# arm_mcu.net
KiCad netlist of a schematic drawn in Altium Designer
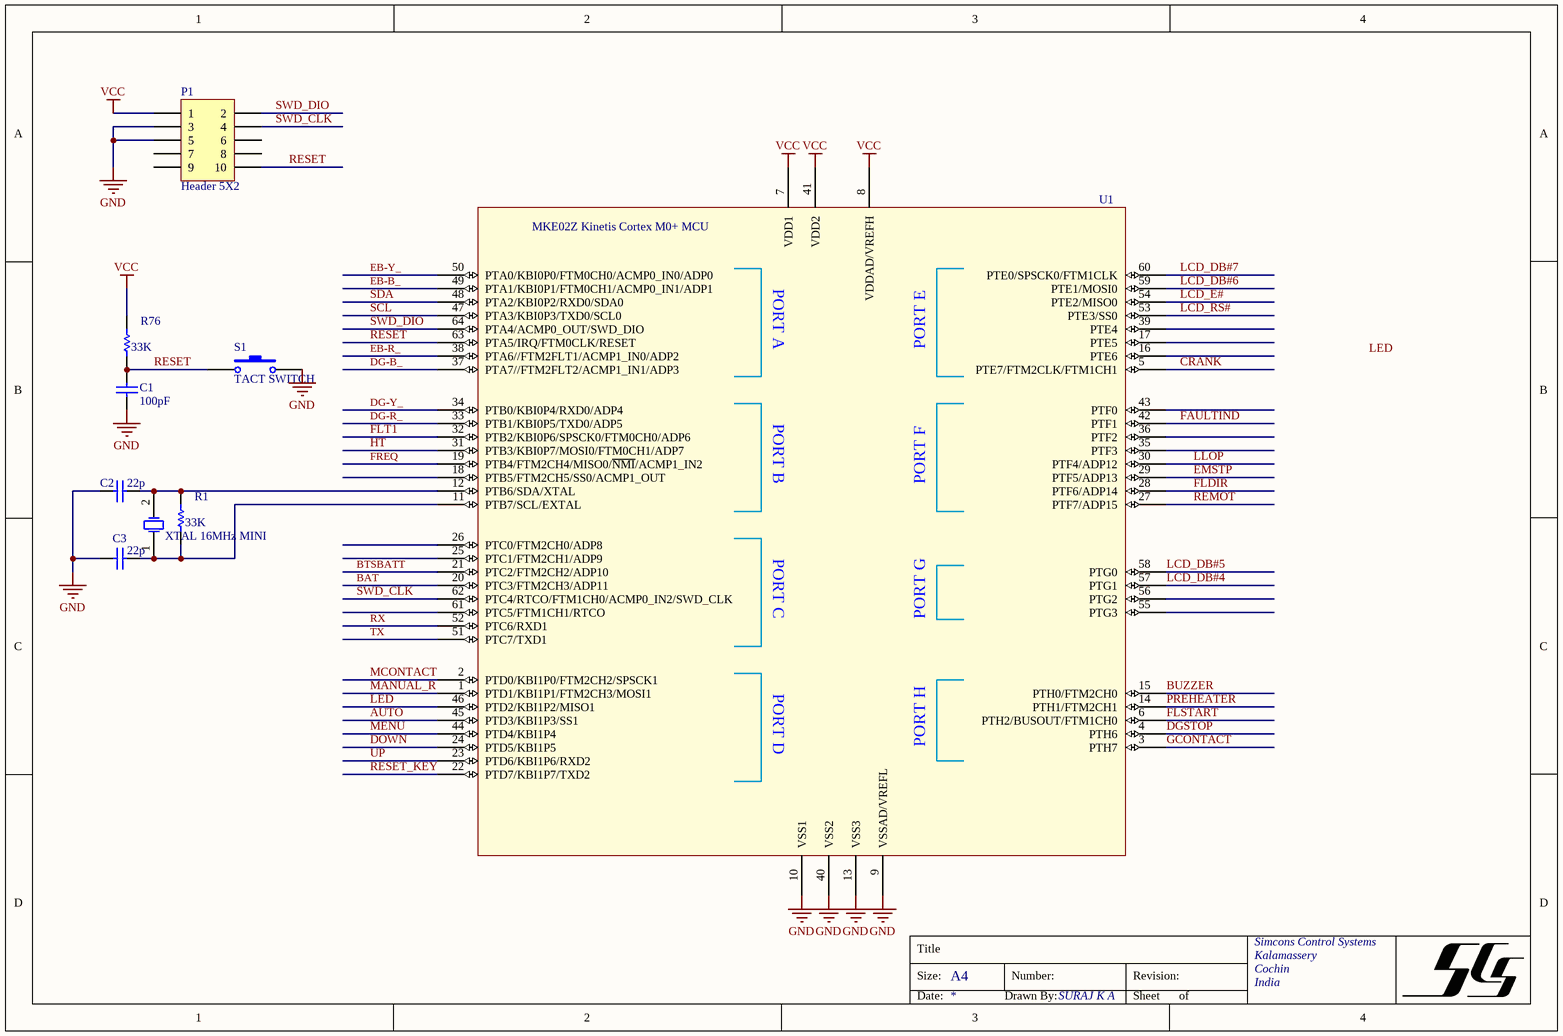
[diagram p0: arm_mcu.SchDoc]

(export (version "E")
  (design (tool "Eeschema 10.0.6"))
  (components
    (comp (ref "C1")
      (value "100pF")
      (footprint "C1206_W")
      (description "Capacitor")
      (fields (field (name "Comment") ".1uF 1206") (field (name "PUBLISHER") "Altium Limited"))
      (libsource (lib "Miscellaneous Devices") (part "Cap"))
    )
    (comp (ref "C2")
      (value "22p")
      (footprint "C1206_W")
      (description "Capacitor")
      (fields (field (name "Comment") "22pF 1206") (field (name "PUBLISHER") "Altium Limited"))
      (libsource (lib "Miscellaneous Devices") (part "Cap"))
    )
    (comp (ref "C3")
      (value "22p")
      (footprint "C1206_W")
      (description "Capacitor")
      (fields (field (name "Comment") "22pF 1206") (field (name "PUBLISHER") "Altium Limited"))
      (libsource (lib "Miscellaneous Devices") (part "Cap"))
    )
    (comp (ref "P1")
      (value "Header 5X2")
      (footprint "HDR2X5")
      (description "Header, 5-Pin, Dual row")
      (fields (field (name "PUBLISHER") "Altium Limited"))
      (libsource (lib "Miscellaneous Connectors") (part "Header 5X2"))
    )
    (comp (ref "R1")
      (value "33K")
      (footprint "R1206_W")
      (description "Resistor")
      (fields (field (name "Comment") "100K 1206") (field (name "PUBLISHER") "Altium Limited"))
      (libsource (lib "Miscellaneous Devices") (part "Res1"))
    )
    (comp (ref "R76")
      (value "33K")
      (footprint "R1206_W")
      (description "Resistor")
      (fields (field (name "Comment") "100K 1206") (field (name "PUBLISHER") "Altium Limited"))
      (libsource (lib "Miscellaneous Devices") (part "Res1"))
    )
    (comp (ref "S1")
      (value "TACT SWITCH")
      (footprint "SWSMALL")
      (description "Switch")
      (fields (field (name "PUBLISHER") "Altium Limited"))
      (libsource (lib "Miscellaneous Devices") (part "SW-PB"))
    )
    (comp (ref "U1")
      (value "MKE02Z Kinetis Cortex M0+ MCU")
      (footprint "PLQP0064GA-A_M")
      (description "32-Bit ARM Cortex M0+ RISC Core, 64KB Program Flash, 256B EEPROM, 4KB RAM, 64-Pin LQFP")
      (libsource (lib "PCB_Project1") (part "MKE02Z64"))
    )
    (comp (ref "Y1")
      (value "XTAL 16MHz MINI")
      (footprint "XTAL")
      (description "Crystal Oscillator")
      (fields (field (name "PUBLISHER") "Altium Limited"))
      (libsource (lib "Miscellaneous Devices") (part "XTAL"))
    )
  )
  (nets
    (net (code "1") (name "/AUTO") (class "Default")
      (node (ref "U1") (pin "45") (pinfunction "PTD3/KBI1P3/SS1_45") (pintype "bidirectional"))
    )
    (net (code "2") (name "/BAT") (class "Default")
      (node (ref "U1") (pin "20") (pinfunction "PTC3/FTM2CH3/ADP11_20") (pintype "bidirectional"))
    )
    (net (code "3") (name "/BTSBATT") (class "Default")
      (node (ref "U1") (pin "21") (pinfunction "PTC2/FTM2CH2/ADP10_21") (pintype "bidirectional"))
    )
    (net (code "4") (name "/BUZZER") (class "Default")
      (node (ref "U1") (pin "15") (pinfunction "PTH0/FTM2CH0_15") (pintype "bidirectional"))
    )
    (net (code "5") (name "/CRANK") (class "Default")
      (node (ref "U1") (pin "5") (pinfunction "PTE7/FTM2CLK/FTM1CH1_5") (pintype "bidirectional"))
    )
    (net (code "6") (name "/DG-B_") (class "Default")
      (node (ref "U1") (pin "37") (pinfunction "PTA7//FTM2FLT2/ACMP1_IN1/ADP3_37") (pintype "bidirectional"))
    )
    (net (code "7") (name "/DG-R_") (class "Default")
      (node (ref "U1") (pin "33") (pinfunction "PTB1/KBI0P5/TXD0/ADP5_33") (pintype "bidirectional"))
    )
    (net (code "8") (name "/DG-Y_") (class "Default")
      (node (ref "U1") (pin "34") (pinfunction "PTB0/KBI0P4/RXD0/ADP4_34") (pintype "bidirectional"))
    )
    (net (code "9") (name "/DGSTOP") (class "Default")
      (node (ref "U1") (pin "4") (pinfunction "PTH6_4") (pintype "bidirectional"))
    )
    (net (code "10") (name "/DOWN") (class "Default")
      (node (ref "U1") (pin "24") (pinfunction "PTD5/KBI1P5_24") (pintype "bidirectional"))
    )
    (net (code "11") (name "/EB-B_") (class "Default")
      (node (ref "U1") (pin "49") (pinfunction "PTA1/KBI0P1/FTM0CH1/ACMP0_IN1/ADP1_49") (pintype "bidirectional"))
    )
    (net (code "12") (name "/EB-R_") (class "Default")
      (node (ref "U1") (pin "38") (pinfunction "PTA6//FTM2FLT1/ACMP1_IN0/ADP2_38") (pintype "bidirectional"))
    )
    (net (code "13") (name "/EB-Y_") (class "Default")
      (node (ref "U1") (pin "50") (pinfunction "PTA0/KBI0P0/FTM0CH0/ACMP0_IN0/ADP0_50") (pintype "bidirectional"))
    )
    (net (code "14") (name "/EMSTP") (class "Default")
      (node (ref "U1") (pin "29") (pinfunction "PTF5/ADP13_29") (pintype "bidirectional"))
    )
    (net (code "15") (name "/FAULTIND") (class "Default")
      (node (ref "U1") (pin "42") (pinfunction "PTF1_42") (pintype "bidirectional"))
    )
    (net (code "16") (name "/FLDIR") (class "Default")
      (node (ref "U1") (pin "28") (pinfunction "PTF6/ADP14_28") (pintype "bidirectional"))
    )
    (net (code "17") (name "/FLSTART") (class "Default")
      (node (ref "U1") (pin "6") (pinfunction "PTH2/BUSOUT/FTM1CH0_6") (pintype "bidirectional"))
    )
    (net (code "18") (name "/FLT1") (class "Default")
      (node (ref "U1") (pin "32") (pinfunction "PTB2/KBI0P6/SPSCK0/FTM0CH0/ADP6_32") (pintype "bidirectional"))
    )
    (net (code "19") (name "/FREQ") (class "Default")
      (node (ref "U1") (pin "19") (pinfunction "PTB4/FTM2CH4/MISO0/~{NMI}/ACMP1_IN2_19") (pintype "bidirectional"))
    )
    (net (code "20") (name "/GCONTACT") (class "Default")
      (node (ref "U1") (pin "3") (pinfunction "PTH7_3") (pintype "bidirectional"))
    )
    (net (code "21") (name "/HT") (class "Default")
      (node (ref "U1") (pin "31") (pinfunction "PTB3/KBI0P7/MOSI0/FTM0CH1/ADP7_31") (pintype "bidirectional"))
    )
    (net (code "22") (name "/LCD_DB#4") (class "Default")
      (node (ref "U1") (pin "57") (pinfunction "PTG1_57") (pintype "bidirectional"))
    )
    (net (code "23") (name "/LCD_DB#5") (class "Default")
      (node (ref "U1") (pin "58") (pinfunction "PTG0_58") (pintype "bidirectional"))
    )
    (net (code "24") (name "/LCD_DB#6") (class "Default")
      (node (ref "U1") (pin "59") (pinfunction "PTE1/MOSI0_59") (pintype "bidirectional"))
    )
    (net (code "25") (name "/LCD_DB#7") (class "Default")
      (node (ref "U1") (pin "60") (pinfunction "PTE0/SPSCK0/FTM1CLK_60") (pintype "bidirectional"))
    )
    (net (code "26") (name "/LCD_E#") (class "Default")
      (node (ref "U1") (pin "54") (pinfunction "PTE2/MISO0_54") (pintype "bidirectional"))
    )
    (net (code "27") (name "/LCD_RS#") (class "Default")
      (node (ref "U1") (pin "53") (pinfunction "PTE3/SS0_53") (pintype "bidirectional"))
    )
    (net (code "28") (name "/LED") (class "Default")
      (node (ref "U1") (pin "46") (pinfunction "PTD2/KBI1P2/MISO1_46") (pintype "bidirectional"))
    )
    (net (code "29") (name "/LLOP") (class "Default")
      (node (ref "U1") (pin "30") (pinfunction "PTF4/ADP12_30") (pintype "bidirectional"))
    )
    (net (code "30") (name "/MANUAL_R") (class "Default")
      (node (ref "U1") (pin "1") (pinfunction "PTD1/KBI1P1/FTM2CH3/MOSI1_1") (pintype "bidirectional"))
    )
    (net (code "31") (name "/MCONTACT") (class "Default")
      (node (ref "U1") (pin "2") (pinfunction "PTD0/KBI1P0/FTM2CH2/SPSCK1_2") (pintype "bidirectional"))
    )
    (net (code "32") (name "/MENU") (class "Default")
      (node (ref "U1") (pin "44") (pinfunction "PTD4/KBI1P4_44") (pintype "bidirectional"))
    )
    (net (code "33") (name "/PREHEATER") (class "Default")
      (node (ref "U1") (pin "14") (pinfunction "PTH1/FTM2CH1_14") (pintype "bidirectional"))
    )
    (net (code "34") (name "/REMOT") (class "Default")
      (node (ref "U1") (pin "27") (pinfunction "PTF7/ADP15_27") (pintype "bidirectional"))
    )
    (net (code "35") (name "/RESET") (class "Default")
      (node (ref "C1") (pin "2") (pinfunction "2_2") (pintype "passive"))
      (node (ref "P1") (pin "10") (pinfunction "10_10") (pintype "passive"))
      (node (ref "R76") (pin "2") (pinfunction "2_2") (pintype "passive"))
      (node (ref "S1") (pin "1") (pinfunction "1_1") (pintype "passive"))
      (node (ref "U1") (pin "63") (pinfunction "PTA5/IRQ/FTM0CLK/RESET_63") (pintype "bidirectional"))
    )
    (net (code "36") (name "/RESET_KEY") (class "Default")
      (node (ref "U1") (pin "22") (pinfunction "PTD7/KBI1P7/TXD2_22") (pintype "bidirectional"))
    )
    (net (code "37") (name "/RX") (class "Default")
      (node (ref "U1") (pin "52") (pinfunction "PTC6/RXD1_52") (pintype "bidirectional"))
    )
    (net (code "38") (name "/SCL") (class "Default")
      (node (ref "U1") (pin "47") (pinfunction "PTA3/KBI0P3/TXD0/SCL0_47") (pintype "bidirectional"))
    )
    (net (code "39") (name "/SDA") (class "Default")
      (node (ref "U1") (pin "48") (pinfunction "PTA2/KBI0P2/RXD0/SDA0_48") (pintype "bidirectional"))
    )
    (net (code "40") (name "/SWD_CLK") (class "Default")
      (node (ref "P1") (pin "4") (pinfunction "4_4") (pintype "passive"))
      (node (ref "U1") (pin "62") (pinfunction "PTC4/RTCO/FTM1CH0/ACMP0_IN2/SWD_CLK_62") (pintype "bidirectional"))
    )
    (net (code "41") (name "/SWD_DIO") (class "Default")
      (node (ref "P1") (pin "2") (pinfunction "2_2") (pintype "passive"))
      (node (ref "U1") (pin "64") (pinfunction "PTA4/ACMP0_OUT/SWD_DIO_64") (pintype "bidirectional"))
    )
    (net (code "42") (name "/TX") (class "Default")
      (node (ref "U1") (pin "51") (pinfunction "PTC7/TXD1_51") (pintype "bidirectional"))
    )
    (net (code "43") (name "/UP") (class "Default")
      (node (ref "U1") (pin "23") (pinfunction "PTD6/KBI1P6/RXD2_23") (pintype "bidirectional"))
    )
    (net (code "44") (name "GND") (class "Default")
      (node (ref "C1") (pin "1") (pinfunction "1_1") (pintype "passive"))
      (node (ref "C2") (pin "1") (pinfunction "1_1") (pintype "passive"))
      (node (ref "C3") (pin "1") (pinfunction "1_1") (pintype "passive"))
      (node (ref "P1") (pin "3") (pinfunction "3_3") (pintype "passive"))
      (node (ref "P1") (pin "5") (pinfunction "5_5") (pintype "passive"))
      (node (ref "S1") (pin "2") (pinfunction "2_2") (pintype "passive"))
      (node (ref "U1") (pin "10") (pinfunction "VSS1_10") (pintype "power_in"))
      (node (ref "U1") (pin "13") (pinfunction "VSS3_13") (pintype "power_in"))
      (node (ref "U1") (pin "40") (pinfunction "VSS2_40") (pintype "power_in"))
      (node (ref "U1") (pin "9") (pinfunction "VSSAD/VREFL_9") (pintype "power_in"))
    )
    (net (code "45") (name "Net-(U1-PTB6{slash}SDA{slash}XTAL)") (class "Default")
      (node (ref "C2") (pin "2") (pinfunction "2_2") (pintype "passive"))
      (node (ref "R1") (pin "1") (pinfunction "1_1") (pintype "passive"))
      (node (ref "U1") (pin "12") (pinfunction "PTB6/SDA/XTAL_12") (pintype "bidirectional"))
      (node (ref "Y1") (pin "2") (pinfunction "OSC2_2") (pintype "passive"))
    )
    (net (code "46") (name "Net-(U1-PTB7{slash}SCL{slash}EXTAL)") (class "Default")
      (node (ref "C3") (pin "2") (pinfunction "2_2") (pintype "passive"))
      (node (ref "R1") (pin "2") (pinfunction "2_2") (pintype "passive"))
      (node (ref "U1") (pin "11") (pinfunction "PTB7/SCL/EXTAL_11") (pintype "bidirectional"))
      (node (ref "Y1") (pin "1") (pinfunction "OSC1_1") (pintype "passive"))
    )
    (net (code "47") (name "VCC") (class "Default")
      (node (ref "P1") (pin "1") (pinfunction "1_1") (pintype "passive"))
      (node (ref "R76") (pin "1") (pinfunction "1_1") (pintype "passive"))
      (node (ref "U1") (pin "41") (pinfunction "VDD2_41") (pintype "power_in"))
      (node (ref "U1") (pin "7") (pinfunction "VDD1_7") (pintype "power_in"))
      (node (ref "U1") (pin "8") (pinfunction "VDDAD/VREFH_8") (pintype "power_in"))
    )
    (net (code "48") (name "unconnected-(P1-Pad6)") (class "Default")
      (node (ref "P1") (pin "6") (pinfunction "6_6") (pintype "passive"))
    )
    (net (code "49") (name "unconnected-(P1-Pad7)") (class "Default")
      (node (ref "P1") (pin "7") (pinfunction "7_7") (pintype "passive"))
    )
    (net (code "50") (name "unconnected-(P1-Pad8)") (class "Default")
      (node (ref "P1") (pin "8") (pinfunction "8_8") (pintype "passive"))
    )
    (net (code "51") (name "unconnected-(P1-Pad9)") (class "Default")
      (node (ref "P1") (pin "9") (pinfunction "9_9") (pintype "passive"))
    )
    (net (code "52") (name "unconnected-(U1-PTB5{slash}FTM2CH5{slash}SS0{slash}ACMP1_OUT-Pad18)") (class "Default")
      (node (ref "U1") (pin "18") (pinfunction "PTB5/FTM2CH5/SS0/ACMP1_OUT_18") (pintype "bidirectional"))
    )
    (net (code "53") (name "unconnected-(U1-PTC0{slash}FTM2CH0{slash}ADP8-Pad26)") (class "Default")
      (node (ref "U1") (pin "26") (pinfunction "PTC0/FTM2CH0/ADP8_26") (pintype "bidirectional"))
    )
    (net (code "54") (name "unconnected-(U1-PTC1{slash}FTM2CH1{slash}ADP9-Pad25)") (class "Default")
      (node (ref "U1") (pin "25") (pinfunction "PTC1/FTM2CH1/ADP9_25") (pintype "bidirectional"))
    )
    (net (code "55") (name "unconnected-(U1-PTC5{slash}FTM1CH1{slash}RTCO-Pad61)") (class "Default")
      (node (ref "U1") (pin "61") (pinfunction "PTC5/FTM1CH1/RTCO_61") (pintype "bidirectional"))
    )
    (net (code "56") (name "unconnected-(U1-PTE4-Pad39)") (class "Default")
      (node (ref "U1") (pin "39") (pinfunction "PTE4_39") (pintype "bidirectional"))
    )
    (net (code "57") (name "unconnected-(U1-PTE5-Pad17)") (class "Default")
      (node (ref "U1") (pin "17") (pinfunction "PTE5_17") (pintype "bidirectional"))
    )
    (net (code "58") (name "unconnected-(U1-PTE6-Pad16)") (class "Default")
      (node (ref "U1") (pin "16") (pinfunction "PTE6_16") (pintype "bidirectional"))
    )
    (net (code "59") (name "unconnected-(U1-PTF0-Pad43)") (class "Default")
      (node (ref "U1") (pin "43") (pinfunction "PTF0_43") (pintype "bidirectional"))
    )
    (net (code "60") (name "unconnected-(U1-PTF2-Pad36)") (class "Default")
      (node (ref "U1") (pin "36") (pinfunction "PTF2_36") (pintype "bidirectional"))
    )
    (net (code "61") (name "unconnected-(U1-PTF3-Pad35)") (class "Default")
      (node (ref "U1") (pin "35") (pinfunction "PTF3_35") (pintype "bidirectional"))
    )
    (net (code "62") (name "unconnected-(U1-PTG2-Pad56)") (class "Default")
      (node (ref "U1") (pin "56") (pinfunction "PTG2_56") (pintype "bidirectional"))
    )
    (net (code "63") (name "unconnected-(U1-PTG3-Pad55)") (class "Default")
      (node (ref "U1") (pin "55") (pinfunction "PTG3_55") (pintype "bidirectional"))
    )
  )
)
